# ugs_wifi_pendant.net
KiCad netlist of a schematic drawn in Altium Designer
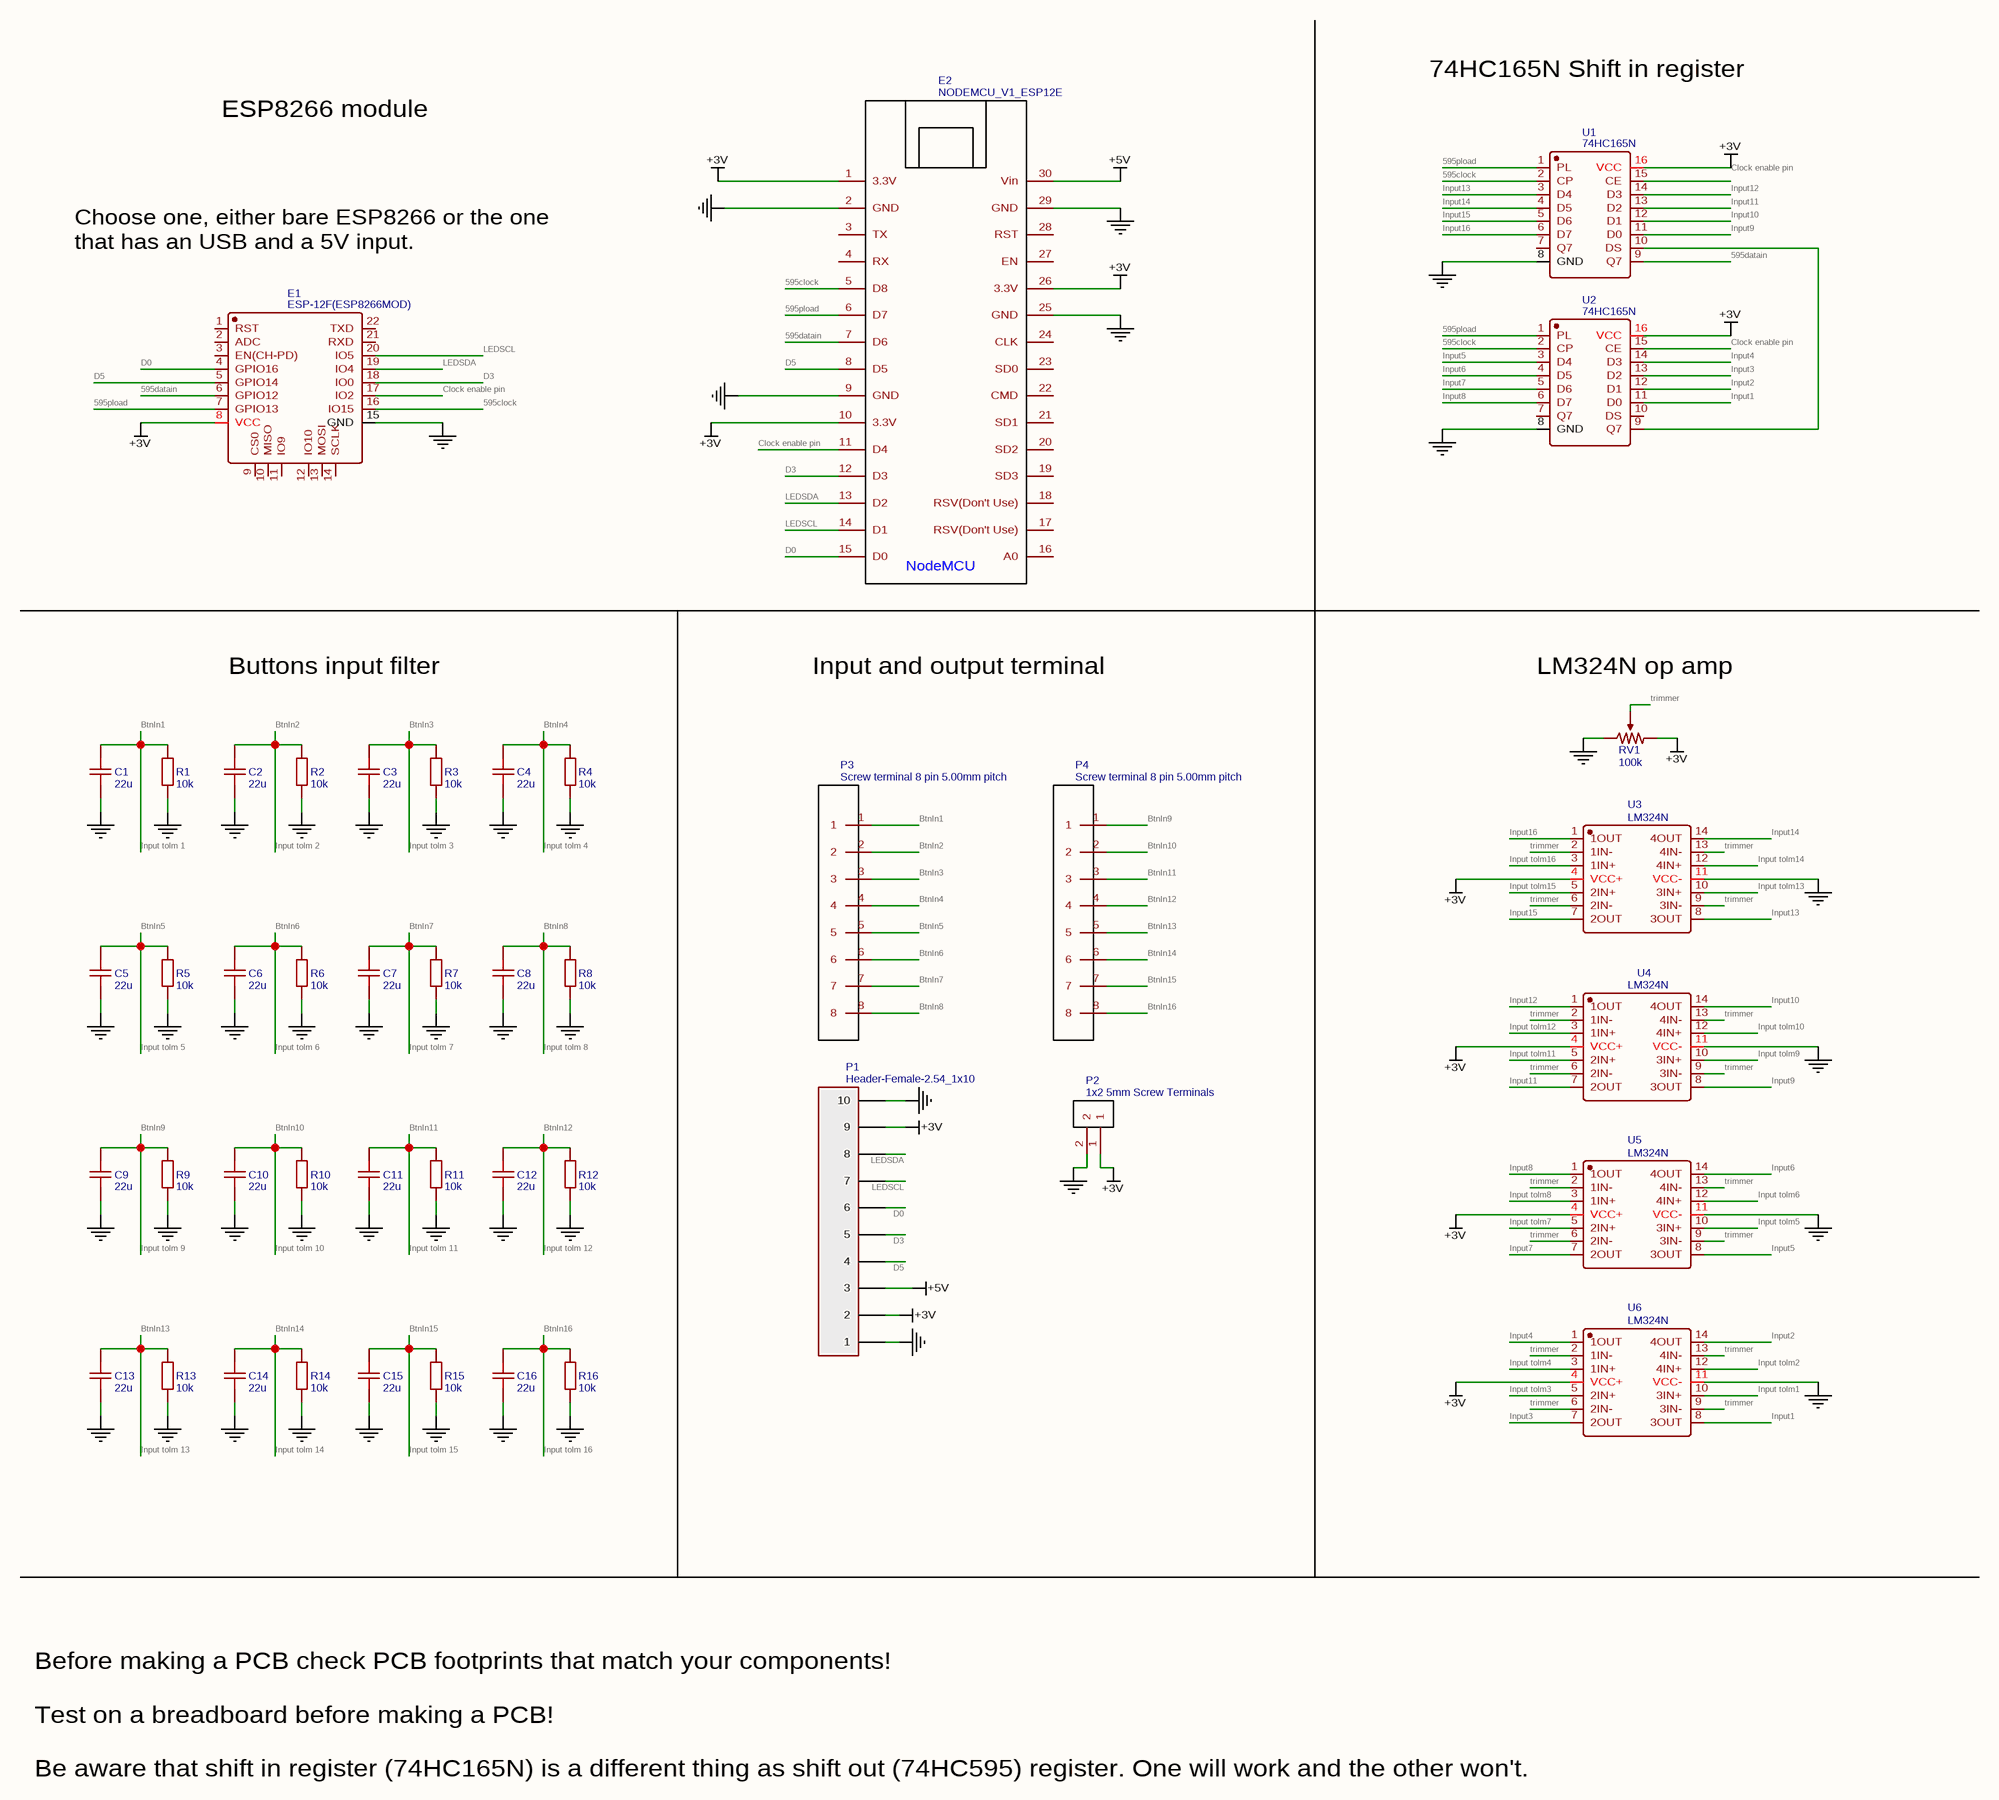
[diagram p0: ugs wifi pendant.schdoc]

(export (version "E")
  (design (tool "Eeschema 10.0.6"))
  (components
    (comp (ref "C1")
      (value "22u")
      (fields (field (name "BOM_MANUFACTURER PART") "?"))
      (libsource (lib "altium-import") (part "root_2_22u_"))
    )
    (comp (ref "C2")
      (value "22u")
      (fields (field (name "BOM_MANUFACTURER PART") "?"))
      (libsource (lib "altium-import") (part "root_2_22u_"))
    )
    (comp (ref "C3")
      (value "22u")
      (fields (field (name "BOM_MANUFACTURER PART") "?"))
      (libsource (lib "altium-import") (part "root_2_22u_"))
    )
    (comp (ref "C4")
      (value "22u")
      (fields (field (name "BOM_MANUFACTURER PART") "?"))
      (libsource (lib "altium-import") (part "root_2_22u_"))
    )
    (comp (ref "C5")
      (value "22u")
      (fields (field (name "BOM_MANUFACTURER PART") "?"))
      (libsource (lib "altium-import") (part "root_2_22u_"))
    )
    (comp (ref "C6")
      (value "22u")
      (fields (field (name "BOM_MANUFACTURER PART") "?"))
      (libsource (lib "altium-import") (part "root_2_22u_"))
    )
    (comp (ref "C7")
      (value "22u")
      (fields (field (name "BOM_MANUFACTURER PART") "?"))
      (libsource (lib "altium-import") (part "root_2_22u_"))
    )
    (comp (ref "C8")
      (value "22u")
      (fields (field (name "BOM_MANUFACTURER PART") "?"))
      (libsource (lib "altium-import") (part "root_2_22u_"))
    )
    (comp (ref "C9")
      (value "22u")
      (fields (field (name "BOM_MANUFACTURER PART") "?"))
      (libsource (lib "altium-import") (part "root_2_22u_"))
    )
    (comp (ref "C10")
      (value "22u")
      (fields (field (name "BOM_MANUFACTURER PART") "?"))
      (libsource (lib "altium-import") (part "root_2_22u_"))
    )
    (comp (ref "C11")
      (value "22u")
      (fields (field (name "BOM_MANUFACTURER PART") "?"))
      (libsource (lib "altium-import") (part "root_2_22u_"))
    )
    (comp (ref "C12")
      (value "22u")
      (fields (field (name "BOM_MANUFACTURER PART") "?"))
      (libsource (lib "altium-import") (part "root_2_22u_"))
    )
    (comp (ref "C13")
      (value "22u")
      (fields (field (name "BOM_MANUFACTURER PART") "?"))
      (libsource (lib "altium-import") (part "root_2_22u_"))
    )
    (comp (ref "C14")
      (value "22u")
      (fields (field (name "BOM_MANUFACTURER PART") "?"))
      (libsource (lib "altium-import") (part "root_2_22u_"))
    )
    (comp (ref "C15")
      (value "22u")
      (fields (field (name "BOM_MANUFACTURER PART") "?"))
      (libsource (lib "altium-import") (part "root_2_22u_"))
    )
    (comp (ref "C16")
      (value "22u")
      (fields (field (name "BOM_MANUFACTURER PART") "?"))
      (libsource (lib "altium-import") (part "root_2_22u_"))
    )
    (comp (ref "E1")
      (value "ESP-12F(ESP8266MOD)")
      (fields (field (name "BOM_SUPPLIER PART") "C82891"))
      (libsource (lib "altium-import") (part "root_0_ESP-12F(ESP8266MOD)_"))
    )
    (comp (ref "E2")
      (value "NODEMCU_V1_ESP12E")
      (fields (field (name "BOM_MANUFACTURER PART") "?") (field (name "CONTRIBUTOR") "canda410"))
      (libsource (lib "altium-import") (part "root_0_NODEMCU_V1_ESP12E_"))
    )
    (comp (ref "P1")
      (value "Header-Female-2.54_1x10")
      (fields (field (name "BOM_SUPPLIER PART") "C35445"))
      (libsource (lib "altium-import") (part "root_2_Header-Female-2.54_1x10_"))
    )
    (comp (ref "P2")
      (value "1x2 5mm Screw Terminals")
      (fields (field (name "CONTRIBUTOR") "IDVert3X"))
      (libsource (lib "altium-import") (part "root_3_1x2 5mm Screw Terminals_"))
    )
    (comp (ref "P3")
      (value "Screw terminal 8 pin 5.00mm pitch")
      (fields (field (name "BOM_MANUFACTURER PART") "?"))
      (libsource (lib "altium-import") (part "root_0_Screw terminal 8 pin 5.00mm pitch_"))
    )
    (comp (ref "P4")
      (value "Screw terminal 8 pin 5.00mm pitch")
      (fields (field (name "BOM_MANUFACTURER PART") "?"))
      (libsource (lib "altium-import") (part "root_0_Screw terminal 8 pin 5.00mm pitch_"))
    )
    (comp (ref "R1")
      (value "10k")
      (fields (field (name "BOM_MANUFACTURER PART") "?"))
      (libsource (lib "altium-import") (part "root_3_10k_"))
    )
    (comp (ref "R2")
      (value "10k")
      (fields (field (name "BOM_MANUFACTURER PART") "?"))
      (libsource (lib "altium-import") (part "root_3_10k_"))
    )
    (comp (ref "R3")
      (value "10k")
      (fields (field (name "BOM_MANUFACTURER PART") "?"))
      (libsource (lib "altium-import") (part "root_3_10k_"))
    )
    (comp (ref "R4")
      (value "10k")
      (fields (field (name "BOM_MANUFACTURER PART") "?"))
      (libsource (lib "altium-import") (part "root_3_10k_"))
    )
    (comp (ref "R5")
      (value "10k")
      (fields (field (name "BOM_MANUFACTURER PART") "?"))
      (libsource (lib "altium-import") (part "root_3_10k_"))
    )
    (comp (ref "R6")
      (value "10k")
      (fields (field (name "BOM_MANUFACTURER PART") "?"))
      (libsource (lib "altium-import") (part "root_3_10k_"))
    )
    (comp (ref "R7")
      (value "10k")
      (fields (field (name "BOM_MANUFACTURER PART") "?"))
      (libsource (lib "altium-import") (part "root_3_10k_"))
    )
    (comp (ref "R8")
      (value "10k")
      (fields (field (name "BOM_MANUFACTURER PART") "?"))
      (libsource (lib "altium-import") (part "root_3_10k_"))
    )
    (comp (ref "R9")
      (value "10k")
      (fields (field (name "BOM_MANUFACTURER PART") "?"))
      (libsource (lib "altium-import") (part "root_3_10k_"))
    )
    (comp (ref "R10")
      (value "10k")
      (fields (field (name "BOM_MANUFACTURER PART") "?"))
      (libsource (lib "altium-import") (part "root_3_10k_"))
    )
    (comp (ref "R11")
      (value "10k")
      (fields (field (name "BOM_MANUFACTURER PART") "?"))
      (libsource (lib "altium-import") (part "root_3_10k_"))
    )
    (comp (ref "R12")
      (value "10k")
      (fields (field (name "BOM_MANUFACTURER PART") "?"))
      (libsource (lib "altium-import") (part "root_3_10k_"))
    )
    (comp (ref "R13")
      (value "10k")
      (fields (field (name "BOM_MANUFACTURER PART") "?"))
      (libsource (lib "altium-import") (part "root_3_10k_"))
    )
    (comp (ref "R14")
      (value "10k")
      (fields (field (name "BOM_MANUFACTURER PART") "?"))
      (libsource (lib "altium-import") (part "root_3_10k_"))
    )
    (comp (ref "R15")
      (value "10k")
      (fields (field (name "BOM_MANUFACTURER PART") "?"))
      (libsource (lib "altium-import") (part "root_3_10k_"))
    )
    (comp (ref "R16")
      (value "10k")
      (fields (field (name "BOM_MANUFACTURER PART") "?"))
      (libsource (lib "altium-import") (part "root_3_10k_"))
    )
    (comp (ref "RV1")
      (value "100k")
      (fields (field (name "BOM_MANUFACTURER PART") "?") (field (name "CONTRIBUTOR") "Lexerar"))
      (libsource (lib "altium-import") (part "root_0_100k_"))
    )
    (comp (ref "U1")
      (value "74HC165N")
      (fields (field (name "BOM_MANUFACTURER PART") "?"))
      (libsource (lib "altium-import") (part "root_0_74HC165N_"))
    )
    (comp (ref "U2")
      (value "74HC165N")
      (fields (field (name "BOM_MANUFACTURER PART") "?"))
      (libsource (lib "altium-import") (part "root_0_74HC165N_"))
    )
    (comp (ref "U3")
      (value "LM324N")
      (fields (field (name "BOM_SUPPLIER PART") "C114380") (field (name "CONTRIBUTOR") "LCSC"))
      (libsource (lib "altium-import") (part "root_0_LM324N_"))
    )
    (comp (ref "U4")
      (value "LM324N")
      (fields (field (name "BOM_SUPPLIER PART") "C114380") (field (name "CONTRIBUTOR") "LCSC"))
      (libsource (lib "altium-import") (part "root_0_LM324N_"))
    )
    (comp (ref "U5")
      (value "LM324N")
      (fields (field (name "BOM_SUPPLIER PART") "C114380") (field (name "CONTRIBUTOR") "LCSC"))
      (libsource (lib "altium-import") (part "root_0_LM324N_"))
    )
    (comp (ref "U6")
      (value "LM324N")
      (fields (field (name "BOM_SUPPLIER PART") "C114380") (field (name "CONTRIBUTOR") "LCSC"))
      (libsource (lib "altium-import") (part "root_0_LM324N_"))
    )
  )
  (nets
    (net (code "1") (name "+3V") (class "Default")
      (node (ref "E1") (pin "8") (pinfunction "VCC_8") (pintype "passive"))
      (node (ref "E2") (pin "1") (pinfunction "3.3V_1") (pintype "passive"))
      (node (ref "E2") (pin "10") (pinfunction "3.3V_10") (pintype "passive"))
      (node (ref "E2") (pin "26") (pinfunction "3.3V_26") (pintype "passive"))
      (node (ref "P1") (pin "2") (pinfunction "2_2") (pintype "passive"))
      (node (ref "P1") (pin "9") (pinfunction "9_9") (pintype "passive"))
      (node (ref "P2") (pin "1") (pinfunction "1_1") (pintype "passive"))
      (node (ref "RV1") (pin "3") (pinfunction "3_3") (pintype "passive"))
      (node (ref "U1") (pin "16") (pinfunction "VCC_16") (pintype "passive"))
      (node (ref "U2") (pin "16") (pinfunction "VCC_16") (pintype "passive"))
      (node (ref "U3") (pin "4") (pinfunction "VCC+_4") (pintype "passive"))
      (node (ref "U4") (pin "4") (pinfunction "VCC+_4") (pintype "passive"))
      (node (ref "U5") (pin "4") (pinfunction "VCC+_4") (pintype "passive"))
      (node (ref "U6") (pin "4") (pinfunction "VCC+_4") (pintype "passive"))
    )
    (net (code "2") (name "+5V") (class "Default")
      (node (ref "E2") (pin "30") (pinfunction "Vin_30") (pintype "passive"))
      (node (ref "P1") (pin "3") (pinfunction "3_3") (pintype "passive"))
    )
    (net (code "3") (name "/595clock") (class "Default")
      (node (ref "E1") (pin "16") (pinfunction "IO15_16") (pintype "passive"))
      (node (ref "E2") (pin "5") (pinfunction "D8_5") (pintype "passive"))
      (node (ref "U1") (pin "2") (pinfunction "CP_2") (pintype "passive"))
      (node (ref "U2") (pin "2") (pinfunction "CP_2") (pintype "passive"))
    )
    (net (code "4") (name "/595datain") (class "Default")
      (node (ref "E1") (pin "6") (pinfunction "GPIO12_6") (pintype "passive"))
      (node (ref "E2") (pin "7") (pinfunction "D6_7") (pintype "passive"))
      (node (ref "U1") (pin "9") (pinfunction "Q7_9") (pintype "passive"))
    )
    (net (code "5") (name "/595pload") (class "Default")
      (node (ref "E1") (pin "7") (pinfunction "GPIO13_7") (pintype "passive"))
      (node (ref "E2") (pin "6") (pinfunction "D7_6") (pintype "passive"))
      (node (ref "U1") (pin "1") (pinfunction "PL_1") (pintype "passive"))
      (node (ref "U2") (pin "1") (pinfunction "PL_1") (pintype "passive"))
    )
    (net (code "6") (name "/BtnIn1") (class "Default")
      (node (ref "P3") (pin "1") (pinfunction "1_1") (pintype "passive"))
    )
    (net (code "7") (name "/BtnIn2") (class "Default")
      (node (ref "P3") (pin "2") (pinfunction "2_2") (pintype "passive"))
    )
    (net (code "8") (name "/BtnIn3") (class "Default")
      (node (ref "P3") (pin "3") (pinfunction "3_3") (pintype "passive"))
    )
    (net (code "9") (name "/BtnIn4") (class "Default")
      (node (ref "P3") (pin "4") (pinfunction "4_4") (pintype "passive"))
    )
    (net (code "10") (name "/BtnIn5") (class "Default")
      (node (ref "P3") (pin "5") (pinfunction "5_5") (pintype "passive"))
    )
    (net (code "11") (name "/BtnIn6") (class "Default")
      (node (ref "P3") (pin "6") (pinfunction "6_6") (pintype "passive"))
    )
    (net (code "12") (name "/BtnIn7") (class "Default")
      (node (ref "P3") (pin "7") (pinfunction "7_7") (pintype "passive"))
    )
    (net (code "13") (name "/BtnIn8") (class "Default")
      (node (ref "P3") (pin "8") (pinfunction "8_8") (pintype "passive"))
    )
    (net (code "14") (name "/BtnIn9") (class "Default")
      (node (ref "P4") (pin "1") (pinfunction "1_1") (pintype "passive"))
    )
    (net (code "15") (name "/BtnIn10") (class "Default")
      (node (ref "P4") (pin "2") (pinfunction "2_2") (pintype "passive"))
    )
    (net (code "16") (name "/BtnIn11") (class "Default")
      (node (ref "P4") (pin "3") (pinfunction "3_3") (pintype "passive"))
    )
    (net (code "17") (name "/BtnIn12") (class "Default")
      (node (ref "P4") (pin "4") (pinfunction "4_4") (pintype "passive"))
    )
    (net (code "18") (name "/BtnIn13") (class "Default")
      (node (ref "P4") (pin "5") (pinfunction "5_5") (pintype "passive"))
    )
    (net (code "19") (name "/BtnIn14") (class "Default")
      (node (ref "P4") (pin "6") (pinfunction "6_6") (pintype "passive"))
    )
    (net (code "20") (name "/BtnIn15") (class "Default")
      (node (ref "P4") (pin "7") (pinfunction "7_7") (pintype "passive"))
    )
    (net (code "21") (name "/BtnIn16") (class "Default")
      (node (ref "P4") (pin "8") (pinfunction "8_8") (pintype "passive"))
    )
    (net (code "22") (name "/Clock enable pin") (class "Default")
      (node (ref "E1") (pin "17") (pinfunction "IO2_17") (pintype "passive"))
      (node (ref "E2") (pin "11") (pinfunction "D4_11") (pintype "passive"))
      (node (ref "U2") (pin "15") (pinfunction "CE_15") (pintype "passive"))
    )
    (net (code "23") (name "/D0") (class "Default")
      (node (ref "E1") (pin "4") (pinfunction "GPIO16_4") (pintype "passive"))
      (node (ref "E2") (pin "15") (pinfunction "D0_15") (pintype "passive"))
      (node (ref "P1") (pin "6") (pinfunction "6_6") (pintype "passive"))
    )
    (net (code "24") (name "/D3") (class "Default")
      (node (ref "E1") (pin "18") (pinfunction "IO0_18") (pintype "passive"))
      (node (ref "E2") (pin "12") (pinfunction "D3_12") (pintype "passive"))
      (node (ref "P1") (pin "5") (pinfunction "5_5") (pintype "passive"))
    )
    (net (code "25") (name "/D5") (class "Default")
      (node (ref "E1") (pin "5") (pinfunction "GPIO14_5") (pintype "passive"))
      (node (ref "E2") (pin "8") (pinfunction "D5_8") (pintype "passive"))
      (node (ref "P1") (pin "4") (pinfunction "4_4") (pintype "passive"))
    )
    (net (code "26") (name "/Input tolm1") (class "Default")
      (node (ref "U6") (pin "10") (pinfunction "3IN+_10") (pintype "passive"))
    )
    (net (code "27") (name "/Input tolm2") (class "Default")
      (node (ref "U6") (pin "12") (pinfunction "4IN+_12") (pintype "passive"))
    )
    (net (code "28") (name "/Input tolm3") (class "Default")
      (node (ref "U6") (pin "5") (pinfunction "2IN+_5") (pintype "passive"))
    )
    (net (code "29") (name "/Input tolm4") (class "Default")
      (node (ref "U6") (pin "3") (pinfunction "1IN+_3") (pintype "passive"))
    )
    (net (code "30") (name "/Input tolm5") (class "Default")
      (node (ref "U5") (pin "10") (pinfunction "3IN+_10") (pintype "passive"))
    )
    (net (code "31") (name "/Input tolm6") (class "Default")
      (node (ref "U5") (pin "12") (pinfunction "4IN+_12") (pintype "passive"))
    )
    (net (code "32") (name "/Input tolm7") (class "Default")
      (node (ref "U5") (pin "5") (pinfunction "2IN+_5") (pintype "passive"))
    )
    (net (code "33") (name "/Input tolm8") (class "Default")
      (node (ref "U5") (pin "3") (pinfunction "1IN+_3") (pintype "passive"))
    )
    (net (code "34") (name "/Input tolm9") (class "Default")
      (node (ref "U4") (pin "10") (pinfunction "3IN+_10") (pintype "passive"))
    )
    (net (code "35") (name "/Input tolm10") (class "Default")
      (node (ref "U4") (pin "12") (pinfunction "4IN+_12") (pintype "passive"))
    )
    (net (code "36") (name "/Input tolm11") (class "Default")
      (node (ref "U4") (pin "5") (pinfunction "2IN+_5") (pintype "passive"))
    )
    (net (code "37") (name "/Input tolm12") (class "Default")
      (node (ref "U4") (pin "3") (pinfunction "1IN+_3") (pintype "passive"))
    )
    (net (code "38") (name "/Input tolm13") (class "Default")
      (node (ref "U3") (pin "10") (pinfunction "3IN+_10") (pintype "passive"))
    )
    (net (code "39") (name "/Input tolm14") (class "Default")
      (node (ref "U3") (pin "12") (pinfunction "4IN+_12") (pintype "passive"))
    )
    (net (code "40") (name "/Input tolm15") (class "Default")
      (node (ref "U3") (pin "5") (pinfunction "2IN+_5") (pintype "passive"))
    )
    (net (code "41") (name "/Input tolm16") (class "Default")
      (node (ref "U3") (pin "3") (pinfunction "1IN+_3") (pintype "passive"))
    )
    (net (code "42") (name "/Input1") (class "Default")
      (node (ref "U2") (pin "11") (pinfunction "D0_11") (pintype "passive"))
      (node (ref "U6") (pin "8") (pinfunction "3OUT_8") (pintype "passive"))
    )
    (net (code "43") (name "/Input2") (class "Default")
      (node (ref "U2") (pin "12") (pinfunction "D1_12") (pintype "passive"))
      (node (ref "U6") (pin "14") (pinfunction "4OUT_14") (pintype "passive"))
    )
    (net (code "44") (name "/Input3") (class "Default")
      (node (ref "U2") (pin "13") (pinfunction "D2_13") (pintype "passive"))
      (node (ref "U6") (pin "7") (pinfunction "2OUT_7") (pintype "passive"))
    )
    (net (code "45") (name "/Input4") (class "Default")
      (node (ref "U2") (pin "14") (pinfunction "D3_14") (pintype "passive"))
      (node (ref "U6") (pin "1") (pinfunction "1OUT_1") (pintype "passive"))
    )
    (net (code "46") (name "/Input5") (class "Default")
      (node (ref "U2") (pin "3") (pinfunction "D4_3") (pintype "passive"))
      (node (ref "U5") (pin "8") (pinfunction "3OUT_8") (pintype "passive"))
    )
    (net (code "47") (name "/Input6") (class "Default")
      (node (ref "U2") (pin "4") (pinfunction "D5_4") (pintype "passive"))
      (node (ref "U5") (pin "14") (pinfunction "4OUT_14") (pintype "passive"))
    )
    (net (code "48") (name "/Input7") (class "Default")
      (node (ref "U2") (pin "5") (pinfunction "D6_5") (pintype "passive"))
      (node (ref "U5") (pin "7") (pinfunction "2OUT_7") (pintype "passive"))
    )
    (net (code "49") (name "/Input8") (class "Default")
      (node (ref "U2") (pin "6") (pinfunction "D7_6") (pintype "passive"))
      (node (ref "U5") (pin "1") (pinfunction "1OUT_1") (pintype "passive"))
    )
    (net (code "50") (name "/Input9") (class "Default")
      (node (ref "U1") (pin "11") (pinfunction "D0_11") (pintype "passive"))
      (node (ref "U4") (pin "8") (pinfunction "3OUT_8") (pintype "passive"))
    )
    (net (code "51") (name "/Input10") (class "Default")
      (node (ref "U1") (pin "12") (pinfunction "D1_12") (pintype "passive"))
      (node (ref "U4") (pin "14") (pinfunction "4OUT_14") (pintype "passive"))
    )
    (net (code "52") (name "/Input11") (class "Default")
      (node (ref "U1") (pin "13") (pinfunction "D2_13") (pintype "passive"))
      (node (ref "U4") (pin "7") (pinfunction "2OUT_7") (pintype "passive"))
    )
    (net (code "53") (name "/Input12") (class "Default")
      (node (ref "U1") (pin "14") (pinfunction "D3_14") (pintype "passive"))
      (node (ref "U4") (pin "1") (pinfunction "1OUT_1") (pintype "passive"))
    )
    (net (code "54") (name "/Input13") (class "Default")
      (node (ref "U1") (pin "3") (pinfunction "D4_3") (pintype "passive"))
      (node (ref "U3") (pin "8") (pinfunction "3OUT_8") (pintype "passive"))
    )
    (net (code "55") (name "/Input14") (class "Default")
      (node (ref "U1") (pin "4") (pinfunction "D5_4") (pintype "passive"))
      (node (ref "U3") (pin "14") (pinfunction "4OUT_14") (pintype "passive"))
    )
    (net (code "56") (name "/Input15") (class "Default")
      (node (ref "U1") (pin "5") (pinfunction "D6_5") (pintype "passive"))
      (node (ref "U3") (pin "7") (pinfunction "2OUT_7") (pintype "passive"))
    )
    (net (code "57") (name "/Input16") (class "Default")
      (node (ref "U1") (pin "6") (pinfunction "D7_6") (pintype "passive"))
      (node (ref "U3") (pin "1") (pinfunction "1OUT_1") (pintype "passive"))
    )
    (net (code "58") (name "/LEDSCL") (class "Default")
      (node (ref "E1") (pin "20") (pinfunction "IO5_20") (pintype "passive"))
      (node (ref "E2") (pin "14") (pinfunction "D1_14") (pintype "passive"))
      (node (ref "P1") (pin "7") (pinfunction "7_7") (pintype "passive"))
    )
    (net (code "59") (name "/LEDSDA") (class "Default")
      (node (ref "E1") (pin "19") (pinfunction "IO4_19") (pintype "passive"))
      (node (ref "E2") (pin "13") (pinfunction "D2_13") (pintype "passive"))
      (node (ref "P1") (pin "8") (pinfunction "8_8") (pintype "passive"))
    )
    (net (code "60") (name "/trimmer") (class "Default")
      (node (ref "RV1") (pin "2") (pinfunction "2_2") (pintype "passive"))
      (node (ref "U3") (pin "13") (pinfunction "4IN-_13") (pintype "passive"))
      (node (ref "U3") (pin "2") (pinfunction "1IN-_2") (pintype "passive"))
      (node (ref "U3") (pin "6") (pinfunction "2IN-_6") (pintype "passive"))
      (node (ref "U3") (pin "9") (pinfunction "3IN-_9") (pintype "passive"))
      (node (ref "U4") (pin "13") (pinfunction "4IN-_13") (pintype "passive"))
      (node (ref "U4") (pin "2") (pinfunction "1IN-_2") (pintype "passive"))
      (node (ref "U4") (pin "6") (pinfunction "2IN-_6") (pintype "passive"))
      (node (ref "U4") (pin "9") (pinfunction "3IN-_9") (pintype "passive"))
      (node (ref "U5") (pin "13") (pinfunction "4IN-_13") (pintype "passive"))
      (node (ref "U5") (pin "2") (pinfunction "1IN-_2") (pintype "passive"))
      (node (ref "U5") (pin "6") (pinfunction "2IN-_6") (pintype "passive"))
      (node (ref "U5") (pin "9") (pinfunction "3IN-_9") (pintype "passive"))
      (node (ref "U6") (pin "13") (pinfunction "4IN-_13") (pintype "passive"))
      (node (ref "U6") (pin "2") (pinfunction "1IN-_2") (pintype "passive"))
      (node (ref "U6") (pin "6") (pinfunction "2IN-_6") (pintype "passive"))
      (node (ref "U6") (pin "9") (pinfunction "3IN-_9") (pintype "passive"))
    )
    (net (code "61") (name "GND") (class "Default")
      (node (ref "E1") (pin "15") (pinfunction "GND_15") (pintype "passive"))
      (node (ref "E2") (pin "2") (pinfunction "GND_2") (pintype "passive"))
      (node (ref "E2") (pin "25") (pinfunction "GND_25") (pintype "passive"))
      (node (ref "E2") (pin "29") (pinfunction "GND_29") (pintype "passive"))
      (node (ref "E2") (pin "9") (pinfunction "GND_9") (pintype "passive"))
      (node (ref "P1") (pin "1") (pinfunction "1_1") (pintype "passive"))
      (node (ref "P1") (pin "10") (pinfunction "10_10") (pintype "passive"))
      (node (ref "P2") (pin "2") (pinfunction "2_2") (pintype "passive"))
      (node (ref "RV1") (pin "1") (pinfunction "1_1") (pintype "passive"))
      (node (ref "U1") (pin "8") (pinfunction "GND_8") (pintype "passive"))
      (node (ref "U2") (pin "8") (pinfunction "GND_8") (pintype "passive"))
      (node (ref "U3") (pin "11") (pinfunction "VCC-_11") (pintype "passive"))
      (node (ref "U4") (pin "11") (pinfunction "VCC-_11") (pintype "passive"))
      (node (ref "U5") (pin "11") (pinfunction "VCC-_11") (pintype "passive"))
      (node (ref "U6") (pin "11") (pinfunction "VCC-_11") (pintype "passive"))
    )
    (net (code "62") (name "Net-(U1-DS)") (class "Default")
      (node (ref "U1") (pin "10") (pinfunction "DS_10") (pintype "passive"))
      (node (ref "U2") (pin "9") (pinfunction "Q7_9") (pintype "passive"))
    )
    (net (code "63") (name "unconnected-(C1-Pad1)") (class "Default")
      (node (ref "C1") (pin "1") (pinfunction "1_1") (pintype "passive"))
    )
    (net (code "64") (name "unconnected-(C1-Pad2)") (class "Default")
      (node (ref "C1") (pin "2") (pinfunction "2_2") (pintype "passive"))
    )
    (net (code "65") (name "unconnected-(C2-Pad1)") (class "Default")
      (node (ref "C2") (pin "1") (pinfunction "1_1") (pintype "passive"))
    )
    (net (code "66") (name "unconnected-(C2-Pad2)") (class "Default")
      (node (ref "C2") (pin "2") (pinfunction "2_2") (pintype "passive"))
    )
    (net (code "67") (name "unconnected-(C3-Pad1)") (class "Default")
      (node (ref "C3") (pin "1") (pinfunction "1_1") (pintype "passive"))
    )
    (net (code "68") (name "unconnected-(C3-Pad2)") (class "Default")
      (node (ref "C3") (pin "2") (pinfunction "2_2") (pintype "passive"))
    )
    (net (code "69") (name "unconnected-(C4-Pad1)") (class "Default")
      (node (ref "C4") (pin "1") (pinfunction "1_1") (pintype "passive"))
    )
    (net (code "70") (name "unconnected-(C4-Pad2)") (class "Default")
      (node (ref "C4") (pin "2") (pinfunction "2_2") (pintype "passive"))
    )
    (net (code "71") (name "unconnected-(C5-Pad1)") (class "Default")
      (node (ref "C5") (pin "1") (pinfunction "1_1") (pintype "passive"))
    )
    (net (code "72") (name "unconnected-(C5-Pad2)") (class "Default")
      (node (ref "C5") (pin "2") (pinfunction "2_2") (pintype "passive"))
    )
    (net (code "73") (name "unconnected-(C6-Pad1)") (class "Default")
      (node (ref "C6") (pin "1") (pinfunction "1_1") (pintype "passive"))
    )
    (net (code "74") (name "unconnected-(C6-Pad2)") (class "Default")
      (node (ref "C6") (pin "2") (pinfunction "2_2") (pintype "passive"))
    )
    (net (code "75") (name "unconnected-(C7-Pad1)") (class "Default")
      (node (ref "C7") (pin "1") (pinfunction "1_1") (pintype "passive"))
    )
    (net (code "76") (name "unconnected-(C7-Pad2)") (class "Default")
      (node (ref "C7") (pin "2") (pinfunction "2_2") (pintype "passive"))
    )
    (net (code "77") (name "unconnected-(C8-Pad1)") (class "Default")
      (node (ref "C8") (pin "1") (pinfunction "1_1") (pintype "passive"))
    )
    (net (code "78") (name "unconnected-(C8-Pad2)") (class "Default")
      (node (ref "C8") (pin "2") (pinfunction "2_2") (pintype "passive"))
    )
    (net (code "79") (name "unconnected-(C9-Pad1)") (class "Default")
      (node (ref "C9") (pin "1") (pinfunction "1_1") (pintype "passive"))
    )
    (net (code "80") (name "unconnected-(C9-Pad2)") (class "Default")
      (node (ref "C9") (pin "2") (pinfunction "2_2") (pintype "passive"))
    )
    (net (code "81") (name "unconnected-(C10-Pad1)") (class "Default")
      (node (ref "C10") (pin "1") (pinfunction "1_1") (pintype "passive"))
    )
    (net (code "82") (name "unconnected-(C10-Pad2)") (class "Default")
      (node (ref "C10") (pin "2") (pinfunction "2_2") (pintype "passive"))
    )
    (net (code "83") (name "unconnected-(C11-Pad1)") (class "Default")
      (node (ref "C11") (pin "1") (pinfunction "1_1") (pintype "passive"))
    )
    (net (code "84") (name "unconnected-(C11-Pad2)") (class "Default")
      (node (ref "C11") (pin "2") (pinfunction "2_2") (pintype "passive"))
    )
    (net (code "85") (name "unconnected-(C12-Pad1)") (class "Default")
      (node (ref "C12") (pin "1") (pinfunction "1_1") (pintype "passive"))
    )
    (net (code "86") (name "unconnected-(C12-Pad2)") (class "Default")
      (node (ref "C12") (pin "2") (pinfunction "2_2") (pintype "passive"))
    )
    (net (code "87") (name "unconnected-(C13-Pad1)") (class "Default")
      (node (ref "C13") (pin "1") (pinfunction "1_1") (pintype "passive"))
    )
    (net (code "88") (name "unconnected-(C13-Pad2)") (class "Default")
      (node (ref "C13") (pin "2") (pinfunction "2_2") (pintype "passive"))
    )
    (net (code "89") (name "unconnected-(C14-Pad1)") (class "Default")
      (node (ref "C14") (pin "1") (pinfunction "1_1") (pintype "passive"))
    )
    (net (code "90") (name "unconnected-(C14-Pad2)") (class "Default")
      (node (ref "C14") (pin "2") (pinfunction "2_2") (pintype "passive"))
    )
    (net (code "91") (name "unconnected-(C15-Pad1)") (class "Default")
      (node (ref "C15") (pin "1") (pinfunction "1_1") (pintype "passive"))
    )
    (net (code "92") (name "unconnected-(C15-Pad2)") (class "Default")
      (node (ref "C15") (pin "2") (pinfunction "2_2") (pintype "passive"))
    )
    (net (code "93") (name "unconnected-(C16-Pad1)") (class "Default")
      (node (ref "C16") (pin "1") (pinfunction "1_1") (pintype "passive"))
    )
    (net (code "94") (name "unconnected-(C16-Pad2)") (class "Default")
      (node (ref "C16") (pin "2") (pinfunction "2_2") (pintype "passive"))
    )
    (net (code "95") (name "unconnected-(E1-ADC-Pad2)") (class "Default")
      (node (ref "E1") (pin "2") (pinfunction "ADC_2") (pintype "passive"))
    )
    (net (code "96") (name "unconnected-(E1-CS0-Pad9)") (class "Default")
      (node (ref "E1") (pin "9") (pinfunction "CS0_9") (pintype "passive"))
    )
    (net (code "97") (name "unconnected-(E1-EN(CH-PD)-Pad3)") (class "Default")
      (node (ref "E1") (pin "3") (pinfunction "EN(CH-PD)_3") (pintype "passive"))
    )
    (net (code "98") (name "unconnected-(E1-IO9-Pad11)") (class "Default")
      (node (ref "E1") (pin "11") (pinfunction "IO9_11") (pintype "passive"))
    )
    (net (code "99") (name "unconnected-(E1-IO10-Pad12)") (class "Default")
      (node (ref "E1") (pin "12") (pinfunction "IO10_12") (pintype "passive"))
    )
    (net (code "100") (name "unconnected-(E1-MISO-Pad10)") (class "Default")
      (node (ref "E1") (pin "10") (pinfunction "MISO_10") (pintype "passive"))
    )
    (net (code "101") (name "unconnected-(E1-MOSI-Pad13)") (class "Default")
      (node (ref "E1") (pin "13") (pinfunction "MOSI_13") (pintype "passive"))
    )
    (net (code "102") (name "unconnected-(E1-RST-Pad1)") (class "Default")
      (node (ref "E1") (pin "1") (pinfunction "RST_1") (pintype "passive"))
    )
    (net (code "103") (name "unconnected-(E1-RXD-Pad21)") (class "Default")
      (node (ref "E1") (pin "21") (pinfunction "RXD_21") (pintype "passive"))
    )
    (net (code "104") (name "unconnected-(E1-SCLK-Pad14)") (class "Default")
      (node (ref "E1") (pin "14") (pinfunction "SCLK_14") (pintype "passive"))
    )
    (net (code "105") (name "unconnected-(E1-TXD-Pad22)") (class "Default")
      (node (ref "E1") (pin "22") (pinfunction "TXD_22") (pintype "passive"))
    )
    (net (code "106") (name "unconnected-(E2-A0-Pad16)") (class "Default")
      (node (ref "E2") (pin "16") (pinfunction "A0_16") (pintype "passive"))
    )
    (net (code "107") (name "unconnected-(E2-CLK-Pad24)") (class "Default")
      (node (ref "E2") (pin "24") (pinfunction "CLK_24") (pintype "passive"))
    )
    (net (code "108") (name "unconnected-(E2-CMD-Pad22)") (class "Default")
      (node (ref "E2") (pin "22") (pinfunction "CMD_22") (pintype "passive"))
    )
    (net (code "109") (name "unconnected-(E2-EN-Pad27)") (class "Default")
      (node (ref "E2") (pin "27") (pinfunction "EN_27") (pintype "passive"))
    )
    (net (code "110") (name "unconnected-(E2-RST-Pad28)") (class "Default")
      (node (ref "E2") (pin "28") (pinfunction "RST_28") (pintype "passive"))
    )
    (net (code "111") (name "unconnected-(E2-RSV(Don't_Use)-Pad17)") (class "Default")
      (node (ref "E2") (pin "17") (pinfunction "RSV(Don't_Use)_17") (pintype "passive"))
    )
    (net (code "112") (name "unconnected-(E2-RSV(Don't_Use)-Pad18)") (class "Default")
      (node (ref "E2") (pin "18") (pinfunction "RSV(Don't_Use)_18") (pintype "passive"))
    )
    (net (code "113") (name "unconnected-(E2-RX-Pad4)") (class "Default")
      (node (ref "E2") (pin "4") (pinfunction "RX_4") (pintype "passive"))
    )
    (net (code "114") (name "unconnected-(E2-SD0-Pad23)") (class "Default")
      (node (ref "E2") (pin "23") (pinfunction "SD0_23") (pintype "passive"))
    )
    (net (code "115") (name "unconnected-(E2-SD1-Pad21)") (class "Default")
      (node (ref "E2") (pin "21") (pinfunction "SD1_21") (pintype "passive"))
    )
    (net (code "116") (name "unconnected-(E2-SD2-Pad20)") (class "Default")
      (node (ref "E2") (pin "20") (pinfunction "SD2_20") (pintype "passive"))
    )
    (net (code "117") (name "unconnected-(E2-SD3-Pad19)") (class "Default")
      (node (ref "E2") (pin "19") (pinfunction "SD3_19") (pintype "passive"))
    )
    (net (code "118") (name "unconnected-(E2-TX-Pad3)") (class "Default")
      (node (ref "E2") (pin "3") (pinfunction "TX_3") (pintype "passive"))
    )
    (net (code "119") (name "unconnected-(R1-Pad1)") (class "Default")
      (node (ref "R1") (pin "1") (pinfunction "1_1") (pintype "passive"))
    )
    (net (code "120") (name "unconnected-(R1-Pad2)") (class "Default")
      (node (ref "R1") (pin "2") (pinfunction "2_2") (pintype "passive"))
    )
    (net (code "121") (name "unconnected-(R2-Pad1)") (class "Default")
      (node (ref "R2") (pin "1") (pinfunction "1_1") (pintype "passive"))
    )
    (net (code "122") (name "unconnected-(R2-Pad2)") (class "Default")
      (node (ref "R2") (pin "2") (pinfunction "2_2") (pintype "passive"))
    )
    (net (code "123") (name "unconnected-(R3-Pad1)") (class "Default")
      (node (ref "R3") (pin "1") (pinfunction "1_1") (pintype "passive"))
    )
    (net (code "124") (name "unconnected-(R3-Pad2)") (class "Default")
      (node (ref "R3") (pin "2") (pinfunction "2_2") (pintype "passive"))
    )
    (net (code "125") (name "unconnected-(R4-Pad1)") (class "Default")
      (node (ref "R4") (pin "1") (pinfunction "1_1") (pintype "passive"))
    )
    (net (code "126") (name "unconnected-(R4-Pad2)") (class "Default")
      (node (ref "R4") (pin "2") (pinfunction "2_2") (pintype "passive"))
    )
    (net (code "127") (name "unconnected-(R5-Pad1)") (class "Default")
      (node (ref "R5") (pin "1") (pinfunction "1_1") (pintype "passive"))
    )
    (net (code "128") (name "unconnected-(R5-Pad2)") (class "Default")
      (node (ref "R5") (pin "2") (pinfunction "2_2") (pintype "passive"))
    )
    (net (code "129") (name "unconnected-(R6-Pad1)") (class "Default")
      (node (ref "R6") (pin "1") (pinfunction "1_1") (pintype "passive"))
    )
    (net (code "130") (name "unconnected-(R6-Pad2)") (class "Default")
      (node (ref "R6") (pin "2") (pinfunction "2_2") (pintype "passive"))
    )
    (net (code "131") (name "unconnected-(R7-Pad1)") (class "Default")
      (node (ref "R7") (pin "1") (pinfunction "1_1") (pintype "passive"))
    )
    (net (code "132") (name "unconnected-(R7-Pad2)") (class "Default")
      (node (ref "R7") (pin "2") (pinfunction "2_2") (pintype "passive"))
    )
    (net (code "133") (name "unconnected-(R8-Pad1)") (class "Default")
      (node (ref "R8") (pin "1") (pinfunction "1_1") (pintype "passive"))
    )
    (net (code "134") (name "unconnected-(R8-Pad2)") (class "Default")
      (node (ref "R8") (pin "2") (pinfunction "2_2") (pintype "passive"))
    )
    (net (code "135") (name "unconnected-(R9-Pad1)") (class "Default")
      (node (ref "R9") (pin "1") (pinfunction "1_1") (pintype "passive"))
    )
    (net (code "136") (name "unconnected-(R9-Pad2)") (class "Default")
      (node (ref "R9") (pin "2") (pinfunction "2_2") (pintype "passive"))
    )
    (net (code "137") (name "unconnected-(R10-Pad1)") (class "Default")
      (node (ref "R10") (pin "1") (pinfunction "1_1") (pintype "passive"))
    )
    (net (code "138") (name "unconnected-(R10-Pad2)") (class "Default")
      (node (ref "R10") (pin "2") (pinfunction "2_2") (pintype "passive"))
    )
    (net (code "139") (name "unconnected-(R11-Pad1)") (class "Default")
      (node (ref "R11") (pin "1") (pinfunction "1_1") (pintype "passive"))
    )
    (net (code "140") (name "unconnected-(R11-Pad2)") (class "Default")
      (node (ref "R11") (pin "2") (pinfunction "2_2") (pintype "passive"))
    )
    (net (code "141") (name "unconnected-(R12-Pad1)") (class "Default")
      (node (ref "R12") (pin "1") (pinfunction "1_1") (pintype "passive"))
    )
    (net (code "142") (name "unconnected-(R12-Pad2)") (class "Default")
      (node (ref "R12") (pin "2") (pinfunction "2_2") (pintype "passive"))
    )
    (net (code "143") (name "unconnected-(R13-Pad1)") (class "Default")
      (node (ref "R13") (pin "1") (pinfunction "1_1") (pintype "passive"))
    )
    (net (code "144") (name "unconnected-(R13-Pad2)") (class "Default")
      (node (ref "R13") (pin "2") (pinfunction "2_2") (pintype "passive"))
    )
    (net (code "145") (name "unconnected-(R14-Pad1)") (class "Default")
      (node (ref "R14") (pin "1") (pinfunction "1_1") (pintype "passive"))
    )
    (net (code "146") (name "unconnected-(R14-Pad2)") (class "Default")
      (node (ref "R14") (pin "2") (pinfunction "2_2") (pintype "passive"))
    )
    (net (code "147") (name "unconnected-(R15-Pad1)") (class "Default")
      (node (ref "R15") (pin "1") (pinfunction "1_1") (pintype "passive"))
    )
    (net (code "148") (name "unconnected-(R15-Pad2)") (class "Default")
      (node (ref "R15") (pin "2") (pinfunction "2_2") (pintype "passive"))
    )
    (net (code "149") (name "unconnected-(R16-Pad1)") (class "Default")
      (node (ref "R16") (pin "1") (pinfunction "1_1") (pintype "passive"))
    )
    (net (code "150") (name "unconnected-(R16-Pad2)") (class "Default")
      (node (ref "R16") (pin "2") (pinfunction "2_2") (pintype "passive"))
    )
    (net (code "151") (name "unconnected-(U1-CE-Pad15)") (class "Default")
      (node (ref "U1") (pin "15") (pinfunction "CE_15") (pintype "passive"))
    )
    (net (code "152") (name "unconnected-(U1-Q7-Pad7)") (class "Default")
      (node (ref "U1") (pin "7") (pinfunction "Q7_7") (pintype "passive"))
    )
    (net (code "153") (name "unconnected-(U2-DS-Pad10)") (class "Default")
      (node (ref "U2") (pin "10") (pinfunction "DS_10") (pintype "passive"))
    )
    (net (code "154") (name "unconnected-(U2-Q7-Pad7)") (class "Default")
      (node (ref "U2") (pin "7") (pinfunction "Q7_7") (pintype "passive"))
    )
  )
)
